# RS232_Comms.net
KiCad netlist of a schematic drawn in Altium Designer
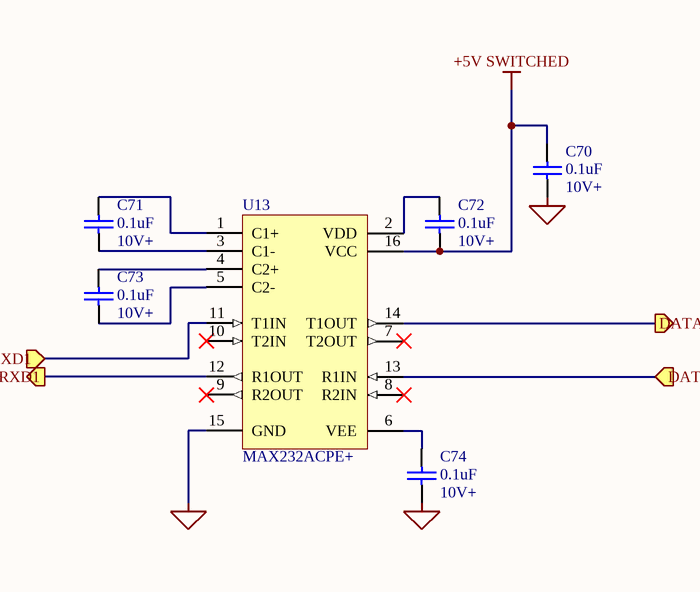
[diagram p0: RS232 Comms.SchDoc]

(export (version "E")
  (design (tool "Eeschema 10.0.6"))
  (components
    (comp (ref "C70")
      (value "0.1uF")
      (footprint "RAD-0.3")
      (description "Capacitor")
      (fields (field (name "PUBLISHER") "Altium Limited"))
      (libsource (lib "Miscellaneous Devices") (part "Cap"))
    )
    (comp (ref "C71")
      (value "0.1uF")
      (footprint "RAD-0.3")
      (description "Capacitor")
      (fields (field (name "PUBLISHER") "Altium Limited"))
      (libsource (lib "Miscellaneous Devices") (part "Cap"))
    )
    (comp (ref "C72")
      (value "0.1uF")
      (footprint "RAD-0.3")
      (description "Capacitor")
      (fields (field (name "PUBLISHER") "Altium Limited"))
      (libsource (lib "Miscellaneous Devices") (part "Cap"))
    )
    (comp (ref "C73")
      (value "0.1uF")
      (footprint "RAD-0.3")
      (description "Capacitor")
      (fields (field (name "PUBLISHER") "Altium Limited"))
      (libsource (lib "Miscellaneous Devices") (part "Cap"))
    )
    (comp (ref "C74")
      (value "0.1uF")
      (footprint "RAD-0.3")
      (description "Capacitor")
      (fields (field (name "PUBLISHER") "Altium Limited"))
      (libsource (lib "Miscellaneous Devices") (part "Cap"))
    )
    (comp (ref "U13")
      (value "MAX232ACPE+")
      (footprint "WSO16_N")
      (description "+5V Powered, Multi-Channel RS-232 Driver/Receiver")
      (fields (field (name "PUBLISHER") "Altium Limited"))
      (libsource (lib "Maxim Communication Transceiver") (part "MAX232ACWE"))
    )
  )
  (nets
    (net (code "1") (name "+5V SWITCHED") (class "Default")
      (node (ref "C70") (pin "2") (pinfunction "2_2") (pintype "passive"))
      (node (ref "C72") (pin "1") (pinfunction "1_1") (pintype "passive"))
      (node (ref "U13") (pin "16") (pinfunction "VCC_16") (pintype "power_in"))
    )
    (net (code "2") (name "/CPU RXD1") (class "Default")
      (node (ref "U13") (pin "12") (pinfunction "R1OUT_12") (pintype "output"))
    )
    (net (code "3") (name "/CPU TXD1") (class "Default")
      (node (ref "U13") (pin "11") (pinfunction "T1IN_11") (pintype "input"))
    )
    (net (code "4") (name "/DATA IN") (class "Default")
      (node (ref "U13") (pin "13") (pinfunction "R1IN_13") (pintype "input"))
    )
    (net (code "5") (name "/DATA OUT") (class "Default")
      (node (ref "U13") (pin "14") (pinfunction "T1OUT_14") (pintype "output"))
    )
    (net (code "6") (name "<NO NET>") (class "Default")
      (node (ref "C70") (pin "1") (pinfunction "1_1") (pintype "passive"))
      (node (ref "C74") (pin "1") (pinfunction "1_1") (pintype "passive"))
      (node (ref "U13") (pin "15") (pinfunction "GND_15") (pintype "power_in"))
    )
    (net (code "7") (name "Net-(U13-C1+)") (class "Default")
      (node (ref "C71") (pin "2") (pinfunction "2_2") (pintype "passive"))
      (node (ref "U13") (pin "1") (pinfunction "C1+_1") (pintype "passive"))
    )
    (net (code "8") (name "Net-(U13-C1-)") (class "Default")
      (node (ref "C71") (pin "1") (pinfunction "1_1") (pintype "passive"))
      (node (ref "U13") (pin "3") (pinfunction "C1-_3") (pintype "passive"))
    )
    (net (code "9") (name "Net-(U13-C2+)") (class "Default")
      (node (ref "C73") (pin "2") (pinfunction "2_2") (pintype "passive"))
      (node (ref "U13") (pin "4") (pinfunction "C2+_4") (pintype "passive"))
    )
    (net (code "10") (name "Net-(U13-C2-)") (class "Default")
      (node (ref "C73") (pin "1") (pinfunction "1_1") (pintype "passive"))
      (node (ref "U13") (pin "5") (pinfunction "C2-_5") (pintype "passive"))
    )
    (net (code "11") (name "Net-(U13-VDD)") (class "Default")
      (node (ref "C72") (pin "2") (pinfunction "2_2") (pintype "passive"))
      (node (ref "U13") (pin "2") (pinfunction "VDD_2") (pintype "power_in"))
    )
    (net (code "12") (name "Net-(U13-VEE)") (class "Default")
      (node (ref "C74") (pin "2") (pinfunction "2_2") (pintype "passive"))
      (node (ref "U13") (pin "6") (pinfunction "VEE_6") (pintype "power_in"))
    )
    (net (code "13") (name "unconnected-(U13-R2IN-Pad8)") (class "Default")
      (node (ref "U13") (pin "8") (pinfunction "R2IN_8") (pintype "input+no_connect"))
    )
    (net (code "14") (name "unconnected-(U13-R2OUT-Pad9)") (class "Default")
      (node (ref "U13") (pin "9") (pinfunction "R2OUT_9") (pintype "output+no_connect"))
    )
    (net (code "15") (name "unconnected-(U13-T2IN-Pad10)") (class "Default")
      (node (ref "U13") (pin "10") (pinfunction "T2IN_10") (pintype "input+no_connect"))
    )
    (net (code "16") (name "unconnected-(U13-T2OUT-Pad7)") (class "Default")
      (node (ref "U13") (pin "7") (pinfunction "T2OUT_7") (pintype "output+no_connect"))
    )
  )
)
